# Sheet5.net
KiCad netlist of a schematic drawn in Altium Designer
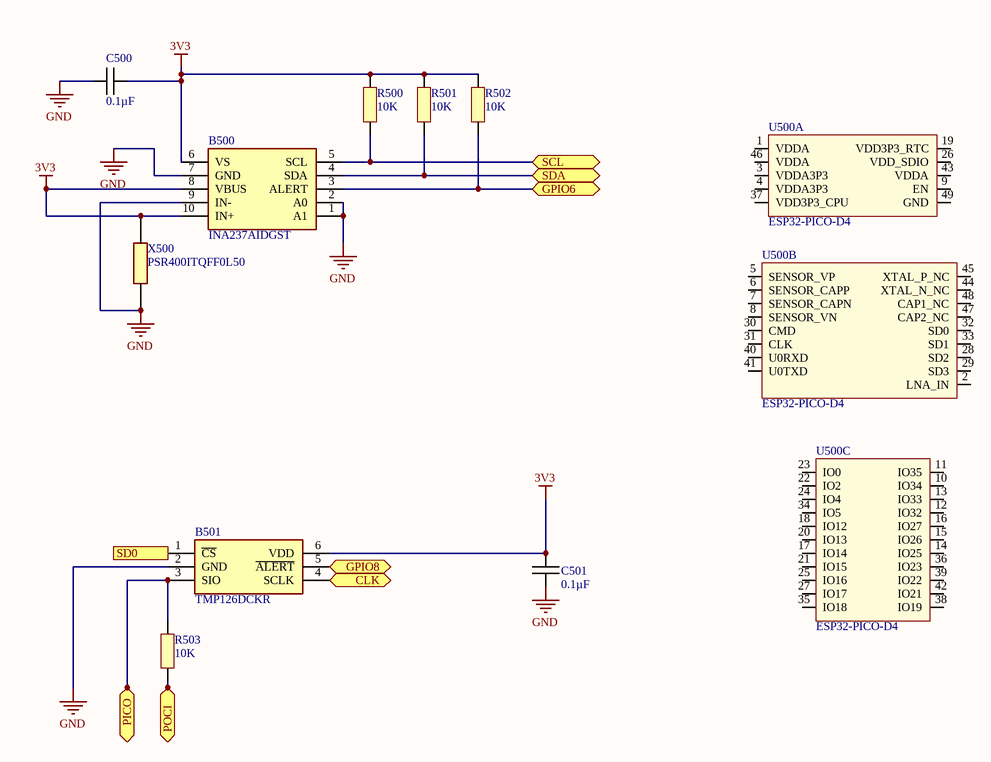
[diagram p0: Sheet5.SchDoc]

(export (version "E")
  (design (tool "Eeschema 10.0.6"))
  (components
    (comp (ref "B500")
      (value "INA237AIDGST")
      (footprint "SOP50P490X110-10N")
      (fields (field (name "MOUSER PART NUMBER") "595-INA237AIDGST"))
      (libsource (lib "SCHLibrary") (part "INA237AIDGST"))
    )
    (comp (ref "B501")
      (value "TMP126DCKR")
      (footprint "SOT65P210X110-6N")
      (fields (field (name "MOUSER PART NUMBER") "595-TMP126DCKR"))
      (libsource (lib "SCHLibrary") (part "TMP126DCKR"))
    )
    (comp (ref "C500")
      (value "0.1µF")
      (footprint "CAPC1005X06N")
      (libsource (lib "SCHLibrary") (part "Capacitor"))
    )
    (comp (ref "C501")
      (value "0.1µF")
      (footprint "CAPC1005X06N")
      (libsource (lib "SCHLibrary") (part "Capacitor"))
    )
    (comp (ref "R500")
      (value "10K")
      (footprint "RESC1005X06N")
      (libsource (lib "SCHLibrary") (part "Resistor"))
    )
    (comp (ref "R501")
      (value "10K")
      (footprint "RESC1005X06N")
      (libsource (lib "SCHLibrary") (part "Resistor"))
    )
    (comp (ref "R502")
      (value "10K")
      (footprint "RESC1005X06N")
      (libsource (lib "SCHLibrary") (part "Resistor"))
    )
    (comp (ref "R503") (value "10K") (footprint "RESC1005X06N") (libsource (lib "") (part "Resistor_1")))
    (comp (ref "U500")
      (value "ESP32-PICO-D4")
      (footprint "PQFN50P700X700X104_HS-49N")
      (libsource (lib "SCHLibrary") (part "ESP32"))
    )
    (comp (ref "X500")
      (value "PSR400ITQFF0L50")
      (footprint "RESC10052X200N")
      (fields (field (name "MOUSER PART NUMBER") "755-PSR400ITQFF0L50"))
      (libsource (lib "SCHLibrary") (part "PSR400ITQFF0L50"))
    )
  )
  (nets
    (net (code "1") (name "/CLK") (class "Default")
      (node (ref "B501") (pin "4") (pinfunction "SCLK_4") (pintype "passive"))
    )
    (net (code "2") (name "/GPIO6") (class "Default")
      (node (ref "B500") (pin "3") (pinfunction "ALERT_3") (pintype "passive"))
      (node (ref "R502") (pin "1") (pinfunction "1_1") (pintype "passive"))
    )
    (net (code "3") (name "/GPIO8") (class "Default")
      (node (ref "B501") (pin "5") (pinfunction "~{ALERT}_5") (pintype "passive"))
    )
    (net (code "4") (name "/PICO") (class "Default")
      (node (ref "B501") (pin "3") (pinfunction "SIO_3") (pintype "passive"))
      (node (ref "R503") (pin "1") (pinfunction "1_1") (pintype "passive"))
    )
    (net (code "5") (name "/POCI") (class "Default")
      (node (ref "R503") (pin "2") (pinfunction "2_2") (pintype "passive"))
    )
    (net (code "6") (name "/SCL") (class "Default")
      (node (ref "B500") (pin "5") (pinfunction "SCL_5") (pintype "passive"))
      (node (ref "R500") (pin "1") (pinfunction "1_1") (pintype "passive"))
    )
    (net (code "7") (name "/SD0") (class "Default")
      (node (ref "B501") (pin "1") (pinfunction "~{CS}_1") (pintype "passive"))
    )
    (net (code "8") (name "/SDA") (class "Default")
      (node (ref "B500") (pin "4") (pinfunction "SDA_4") (pintype "passive"))
      (node (ref "R501") (pin "1") (pinfunction "1_1") (pintype "passive"))
    )
    (net (code "9") (name "3V3") (class "Default")
      (node (ref "B500") (pin "10") (pinfunction "IN+_10") (pintype "passive"))
      (node (ref "B500") (pin "6") (pinfunction "VS_6") (pintype "passive"))
      (node (ref "B500") (pin "8") (pinfunction "VBUS_8") (pintype "passive"))
      (node (ref "B501") (pin "6") (pinfunction "VDD_6") (pintype "passive"))
      (node (ref "C500") (pin "2") (pinfunction "2_2") (pintype "passive"))
      (node (ref "C501") (pin "2") (pinfunction "2_2") (pintype "passive"))
      (node (ref "R500") (pin "2") (pinfunction "2_2") (pintype "passive"))
      (node (ref "R501") (pin "2") (pinfunction "2_2") (pintype "passive"))
      (node (ref "R502") (pin "2") (pinfunction "2_2") (pintype "passive"))
      (node (ref "X500") (pin "2") (pinfunction "2_2") (pintype "passive"))
    )
    (net (code "10") (name "GND") (class "Default")
      (node (ref "B500") (pin "1") (pinfunction "A1_1") (pintype "passive"))
      (node (ref "B500") (pin "2") (pinfunction "A0_2") (pintype "passive"))
      (node (ref "B500") (pin "7") (pinfunction "GND_7") (pintype "passive"))
      (node (ref "B500") (pin "9") (pinfunction "IN-_9") (pintype "passive"))
      (node (ref "B501") (pin "2") (pinfunction "GND_2") (pintype "passive"))
      (node (ref "C500") (pin "1") (pinfunction "1_1") (pintype "passive"))
      (node (ref "C501") (pin "1") (pinfunction "1_1") (pintype "passive"))
      (node (ref "X500") (pin "1") (pinfunction "1_1") (pintype "passive"))
    )
    (net (code "11") (name "unconnected-(U500A-EN-Pad9)") (class "Default")
      (node (ref "U500") (pin "9") (pinfunction "EN_9") (pintype "passive"))
    )
    (net (code "12") (name "unconnected-(U500A-GND-Pad49)") (class "Default")
      (node (ref "U500") (pin "49") (pinfunction "GND_49") (pintype "passive"))
    )
    (net (code "13") (name "unconnected-(U500A-VDD3P3_CPU-Pad37)") (class "Default")
      (node (ref "U500") (pin "37") (pinfunction "VDD3P3_CPU_37") (pintype "passive"))
    )
    (net (code "14") (name "unconnected-(U500A-VDD3P3_RTC-Pad19)") (class "Default")
      (node (ref "U500") (pin "19") (pinfunction "VDD3P3_RTC_19") (pintype "passive"))
    )
    (net (code "15") (name "unconnected-(U500A-VDDA-Pad1)") (class "Default")
      (node (ref "U500") (pin "1") (pinfunction "VDDA_1") (pintype "passive"))
    )
    (net (code "16") (name "unconnected-(U500A-VDDA-Pad43)") (class "Default")
      (node (ref "U500") (pin "43") (pinfunction "VDDA_43") (pintype "passive"))
    )
    (net (code "17") (name "unconnected-(U500A-VDDA-Pad46)") (class "Default")
      (node (ref "U500") (pin "46") (pinfunction "VDDA_46") (pintype "passive"))
    )
    (net (code "18") (name "unconnected-(U500A-VDDA3P3-Pad3)") (class "Default")
      (node (ref "U500") (pin "3") (pinfunction "VDDA3P3_3") (pintype "passive"))
    )
    (net (code "19") (name "unconnected-(U500A-VDDA3P3-Pad4)") (class "Default")
      (node (ref "U500") (pin "4") (pinfunction "VDDA3P3_4") (pintype "passive"))
    )
    (net (code "20") (name "unconnected-(U500A-VDD_SDIO-Pad26)") (class "Default")
      (node (ref "U500") (pin "26") (pinfunction "VDD_SDIO_26") (pintype "passive"))
    )
    (net (code "21") (name "unconnected-(U500B-CAP1_NC-Pad48)") (class "Default")
      (node (ref "U500") (pin "48") (pinfunction "CAP1_NC_48") (pintype "passive"))
    )
    (net (code "22") (name "unconnected-(U500B-CAP2_NC-Pad47)") (class "Default")
      (node (ref "U500") (pin "47") (pinfunction "CAP2_NC_47") (pintype "passive"))
    )
    (net (code "23") (name "unconnected-(U500B-CLK-Pad31)") (class "Default")
      (node (ref "U500") (pin "31") (pinfunction "CLK_31") (pintype "passive"))
    )
    (net (code "24") (name "unconnected-(U500B-CMD-Pad30)") (class "Default")
      (node (ref "U500") (pin "30") (pinfunction "CMD_30") (pintype "passive"))
    )
    (net (code "25") (name "unconnected-(U500B-LNA_IN-Pad2)") (class "Default")
      (node (ref "U500") (pin "2") (pinfunction "LNA_IN_2") (pintype "passive"))
    )
    (net (code "26") (name "unconnected-(U500B-SD0-Pad32)") (class "Default")
      (node (ref "U500") (pin "32") (pinfunction "SD0_32") (pintype "passive"))
    )
    (net (code "27") (name "unconnected-(U500B-SD1-Pad33)") (class "Default")
      (node (ref "U500") (pin "33") (pinfunction "SD1_33") (pintype "passive"))
    )
    (net (code "28") (name "unconnected-(U500B-SD2-Pad28)") (class "Default")
      (node (ref "U500") (pin "28") (pinfunction "SD2_28") (pintype "passive"))
    )
    (net (code "29") (name "unconnected-(U500B-SD3-Pad29)") (class "Default")
      (node (ref "U500") (pin "29") (pinfunction "SD3_29") (pintype "passive"))
    )
    (net (code "30") (name "unconnected-(U500B-SENSOR_CAPN-Pad7)") (class "Default")
      (node (ref "U500") (pin "7") (pinfunction "SENSOR_CAPN_7") (pintype "passive"))
    )
    (net (code "31") (name "unconnected-(U500B-SENSOR_CAPP-Pad6)") (class "Default")
      (node (ref "U500") (pin "6") (pinfunction "SENSOR_CAPP_6") (pintype "passive"))
    )
    (net (code "32") (name "unconnected-(U500B-SENSOR_VN-Pad8)") (class "Default")
      (node (ref "U500") (pin "8") (pinfunction "SENSOR_VN_8") (pintype "passive"))
    )
    (net (code "33") (name "unconnected-(U500B-SENSOR_VP-Pad5)") (class "Default")
      (node (ref "U500") (pin "5") (pinfunction "SENSOR_VP_5") (pintype "passive"))
    )
    (net (code "34") (name "unconnected-(U500B-U0RXD-Pad40)") (class "Default")
      (node (ref "U500") (pin "40") (pinfunction "U0RXD_40") (pintype "passive"))
    )
    (net (code "35") (name "unconnected-(U500B-U0TXD-Pad41)") (class "Default")
      (node (ref "U500") (pin "41") (pinfunction "U0TXD_41") (pintype "passive"))
    )
    (net (code "36") (name "unconnected-(U500B-XTAL_N_NC-Pad44)") (class "Default")
      (node (ref "U500") (pin "44") (pinfunction "XTAL_N_NC_44") (pintype "passive"))
    )
    (net (code "37") (name "unconnected-(U500B-XTAL_P_NC-Pad45)") (class "Default")
      (node (ref "U500") (pin "45") (pinfunction "XTAL_P_NC_45") (pintype "passive"))
    )
    (net (code "38") (name "unconnected-(U500C-IO0-Pad23)") (class "Default")
      (node (ref "U500") (pin "23") (pinfunction "IO0_23") (pintype "passive"))
    )
    (net (code "39") (name "unconnected-(U500C-IO2-Pad22)") (class "Default")
      (node (ref "U500") (pin "22") (pinfunction "IO2_22") (pintype "passive"))
    )
    (net (code "40") (name "unconnected-(U500C-IO4-Pad24)") (class "Default")
      (node (ref "U500") (pin "24") (pinfunction "IO4_24") (pintype "passive"))
    )
    (net (code "41") (name "unconnected-(U500C-IO5-Pad34)") (class "Default")
      (node (ref "U500") (pin "34") (pinfunction "IO5_34") (pintype "passive"))
    )
    (net (code "42") (name "unconnected-(U500C-IO12-Pad18)") (class "Default")
      (node (ref "U500") (pin "18") (pinfunction "IO12_18") (pintype "passive"))
    )
    (net (code "43") (name "unconnected-(U500C-IO13-Pad20)") (class "Default")
      (node (ref "U500") (pin "20") (pinfunction "IO13_20") (pintype "passive"))
    )
    (net (code "44") (name "unconnected-(U500C-IO14-Pad17)") (class "Default")
      (node (ref "U500") (pin "17") (pinfunction "IO14_17") (pintype "passive"))
    )
    (net (code "45") (name "unconnected-(U500C-IO15-Pad21)") (class "Default")
      (node (ref "U500") (pin "21") (pinfunction "IO15_21") (pintype "passive"))
    )
    (net (code "46") (name "unconnected-(U500C-IO16-Pad25)") (class "Default")
      (node (ref "U500") (pin "25") (pinfunction "IO16_25") (pintype "passive"))
    )
    (net (code "47") (name "unconnected-(U500C-IO17-Pad27)") (class "Default")
      (node (ref "U500") (pin "27") (pinfunction "IO17_27") (pintype "passive"))
    )
    (net (code "48") (name "unconnected-(U500C-IO18-Pad35)") (class "Default")
      (node (ref "U500") (pin "35") (pinfunction "IO18_35") (pintype "passive"))
    )
    (net (code "49") (name "unconnected-(U500C-IO19-Pad38)") (class "Default")
      (node (ref "U500") (pin "38") (pinfunction "IO19_38") (pintype "passive"))
    )
    (net (code "50") (name "unconnected-(U500C-IO21-Pad42)") (class "Default")
      (node (ref "U500") (pin "42") (pinfunction "IO21_42") (pintype "passive"))
    )
    (net (code "51") (name "unconnected-(U500C-IO22-Pad39)") (class "Default")
      (node (ref "U500") (pin "39") (pinfunction "IO22_39") (pintype "passive"))
    )
    (net (code "52") (name "unconnected-(U500C-IO23-Pad36)") (class "Default")
      (node (ref "U500") (pin "36") (pinfunction "IO23_36") (pintype "passive"))
    )
    (net (code "53") (name "unconnected-(U500C-IO25-Pad14)") (class "Default")
      (node (ref "U500") (pin "14") (pinfunction "IO25_14") (pintype "passive"))
    )
    (net (code "54") (name "unconnected-(U500C-IO26-Pad15)") (class "Default")
      (node (ref "U500") (pin "15") (pinfunction "IO26_15") (pintype "passive"))
    )
    (net (code "55") (name "unconnected-(U500C-IO27-Pad16)") (class "Default")
      (node (ref "U500") (pin "16") (pinfunction "IO27_16") (pintype "passive"))
    )
    (net (code "56") (name "unconnected-(U500C-IO32-Pad12)") (class "Default")
      (node (ref "U500") (pin "12") (pinfunction "IO32_12") (pintype "passive"))
    )
    (net (code "57") (name "unconnected-(U500C-IO33-Pad13)") (class "Default")
      (node (ref "U500") (pin "13") (pinfunction "IO33_13") (pintype "passive"))
    )
    (net (code "58") (name "unconnected-(U500C-IO34-Pad10)") (class "Default")
      (node (ref "U500") (pin "10") (pinfunction "IO34_10") (pintype "passive"))
    )
    (net (code "59") (name "unconnected-(U500C-IO35-Pad11)") (class "Default")
      (node (ref "U500") (pin "11") (pinfunction "IO35_11") (pintype "passive"))
    )
  )
)
